# SheetV2.net
KiCad netlist of a schematic drawn in Altium Designer
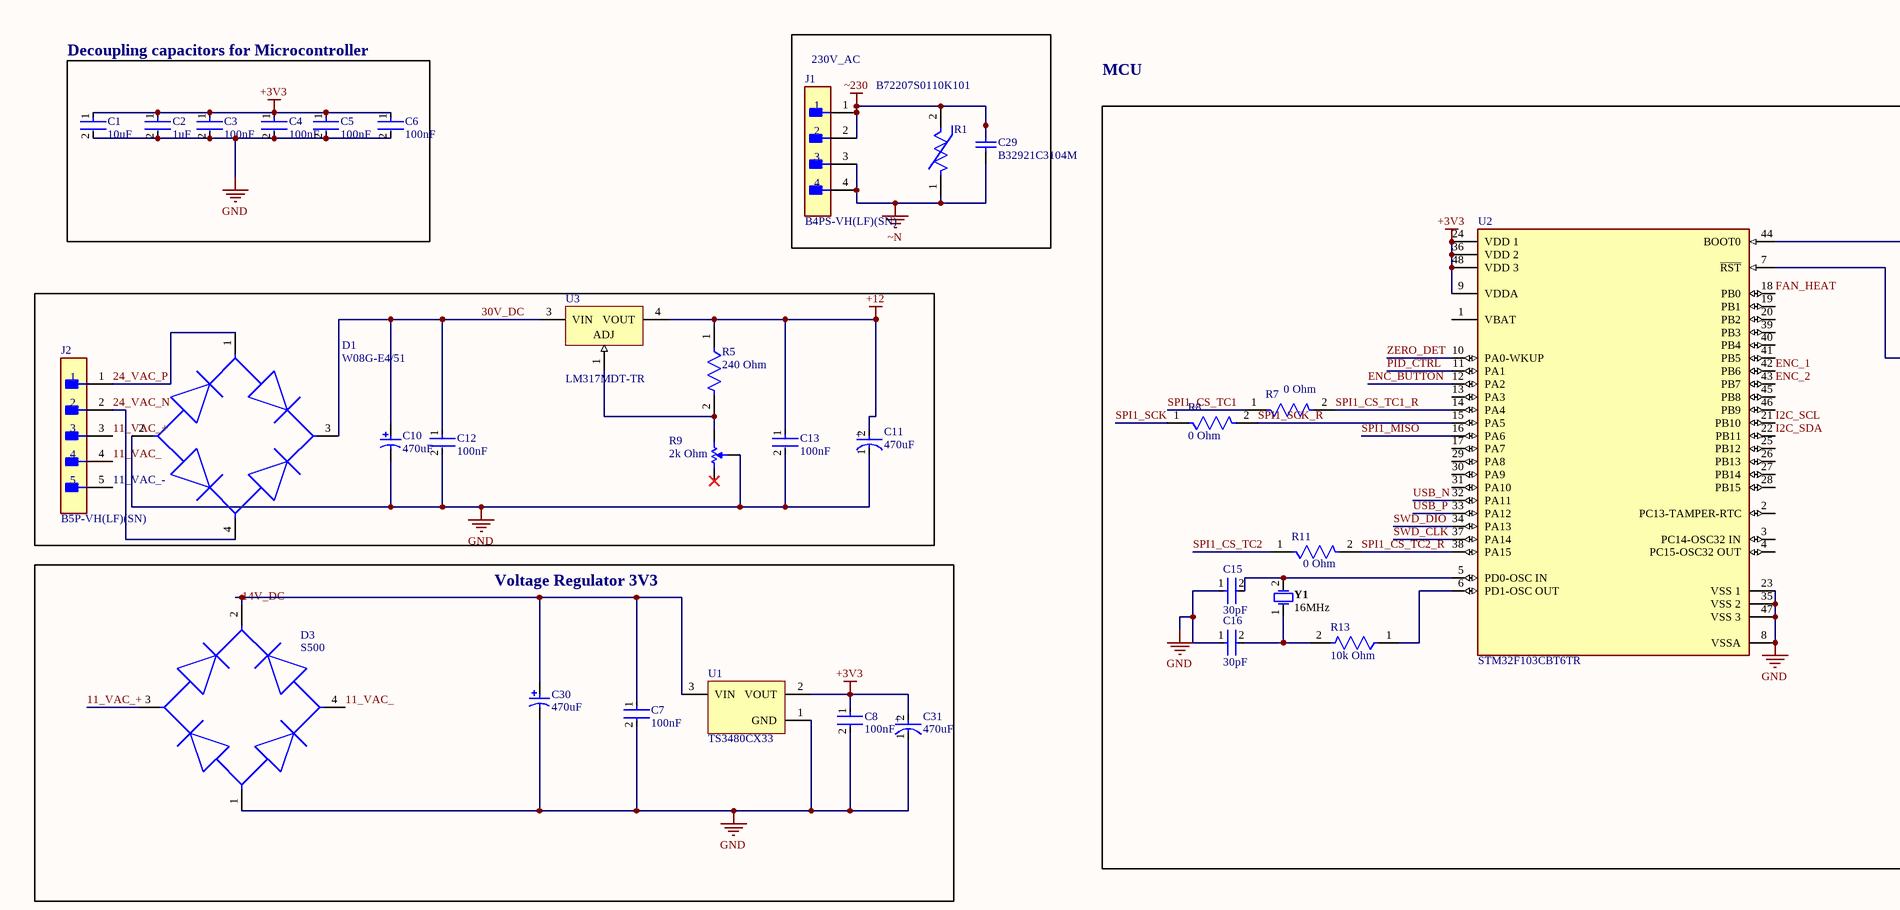
[diagram p0: SheetV2.SchDoc, top left]
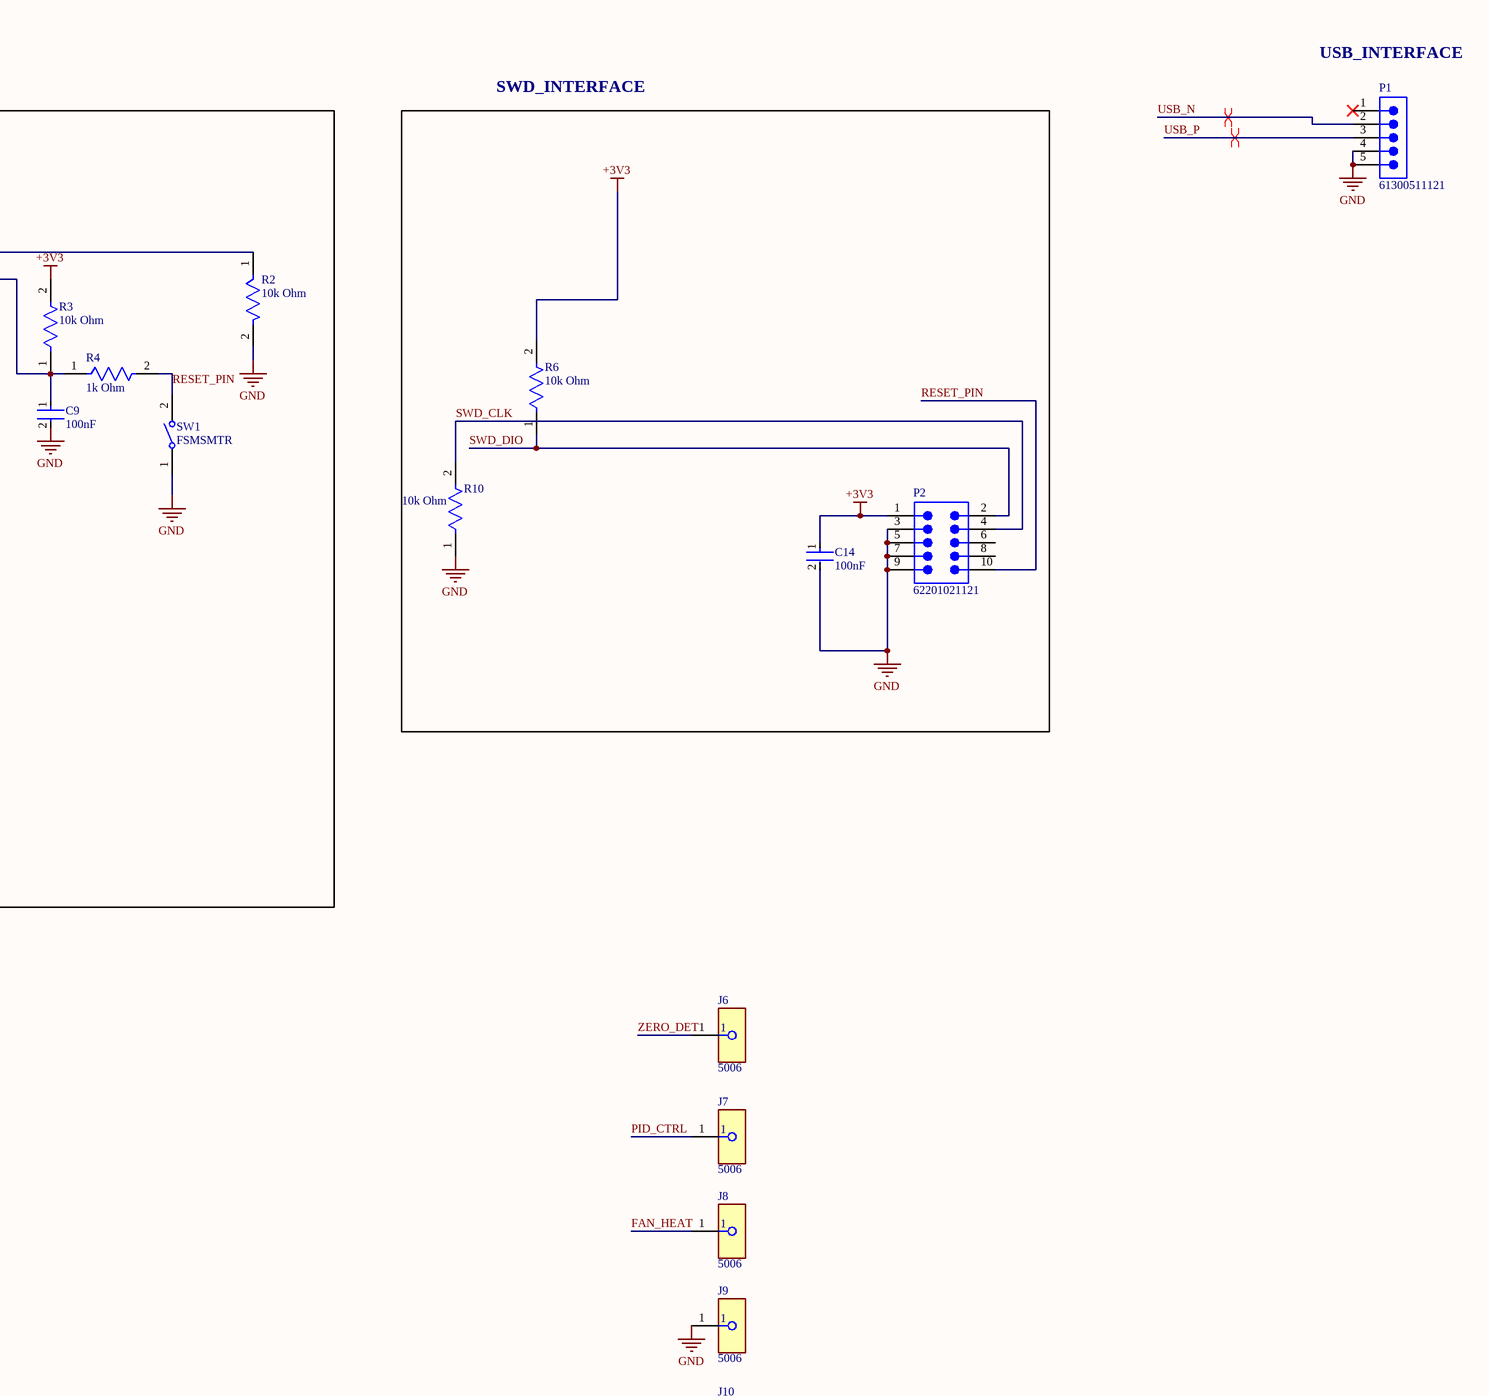
[diagram p1: SheetV2.SchDoc, top right]
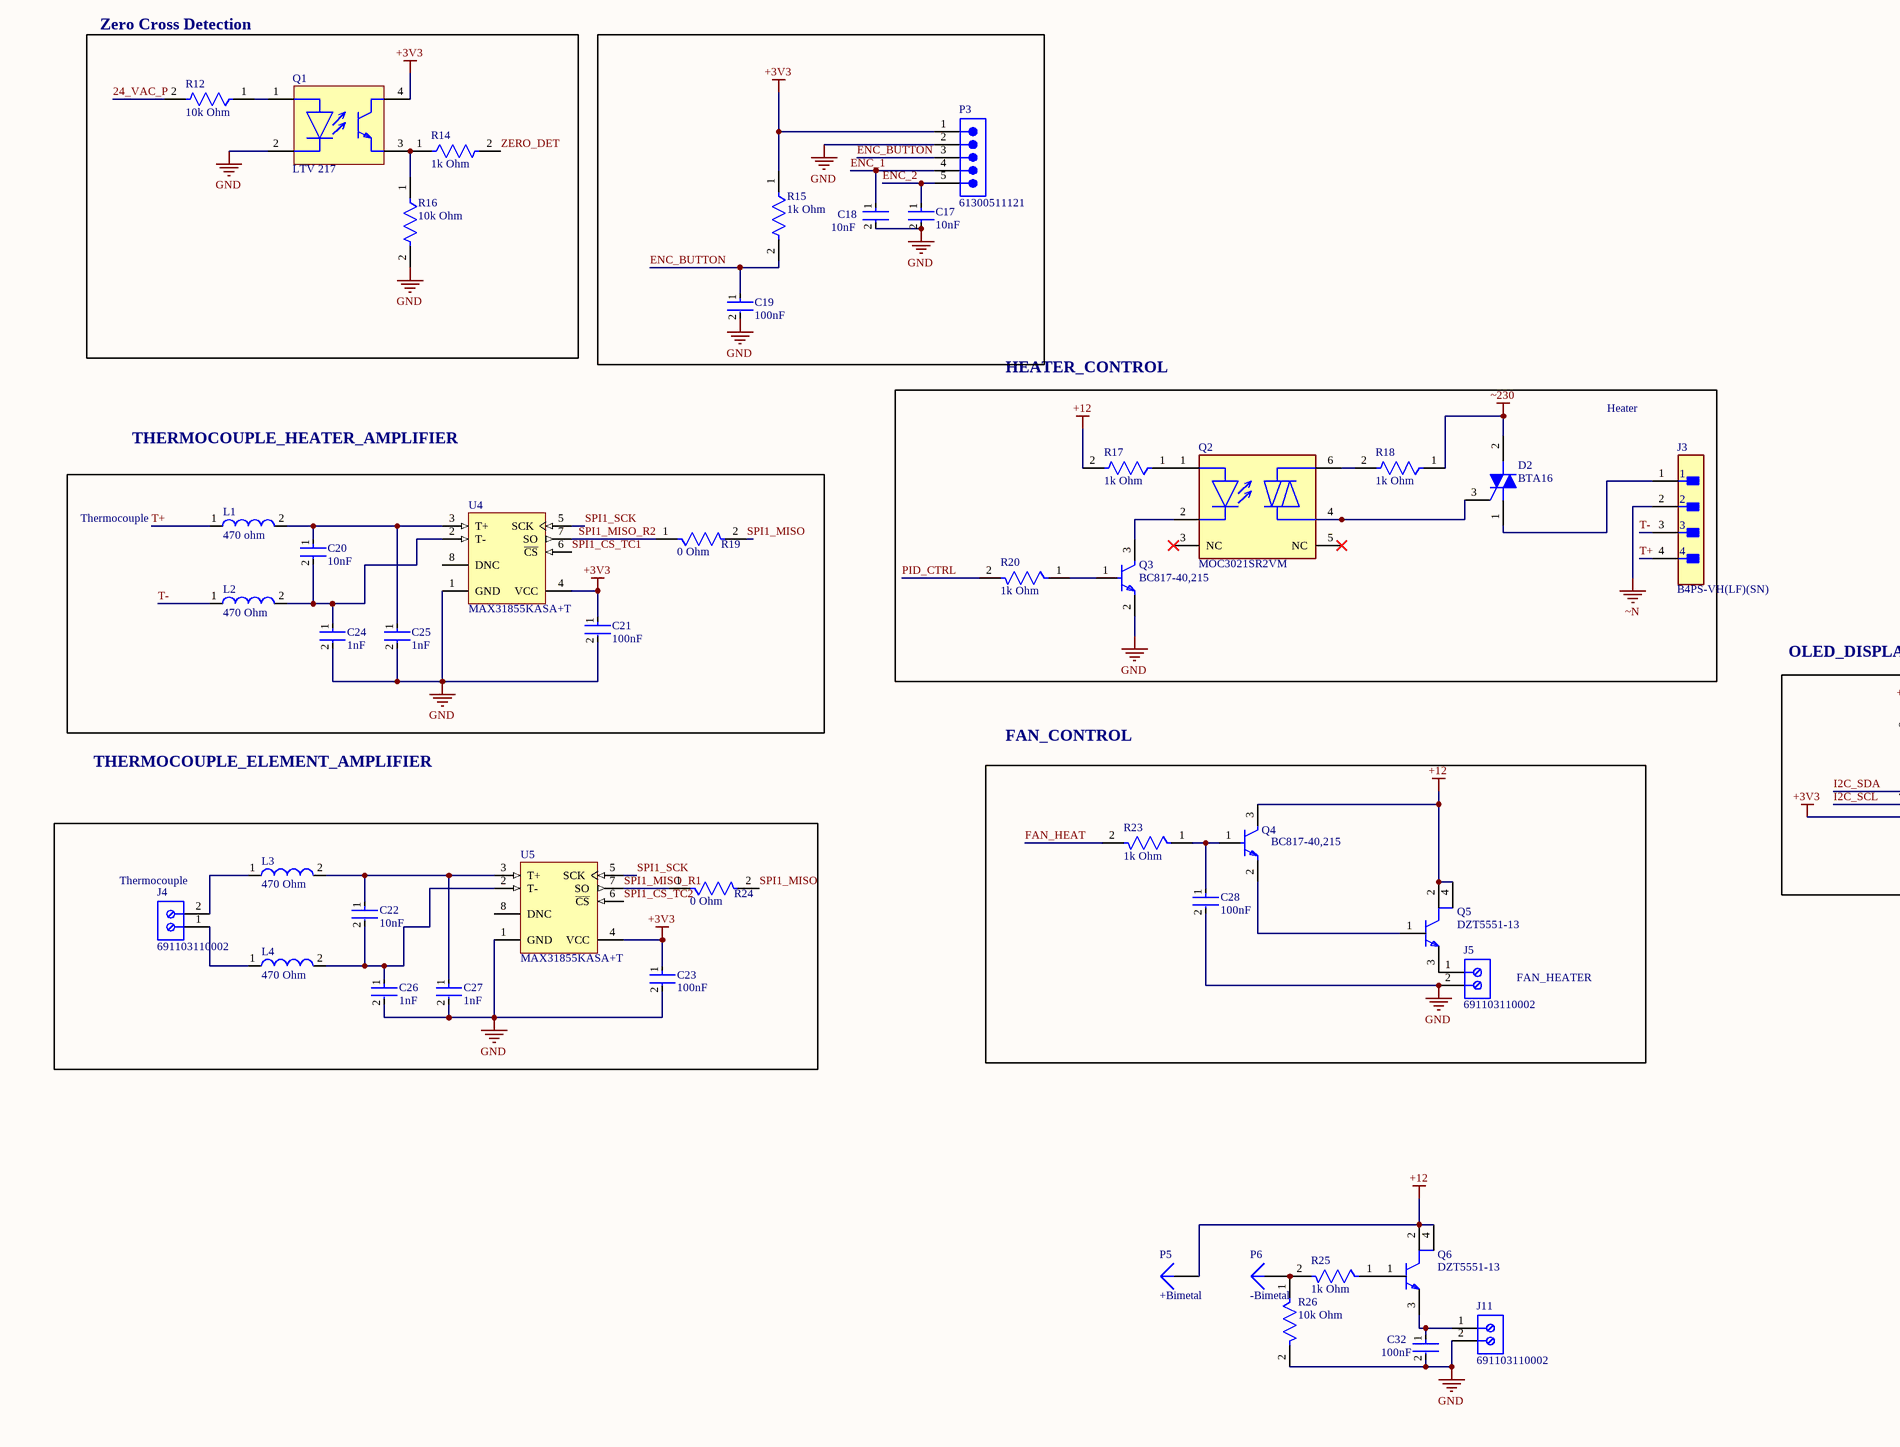
[diagram p2: SheetV2.SchDoc, bottom left]
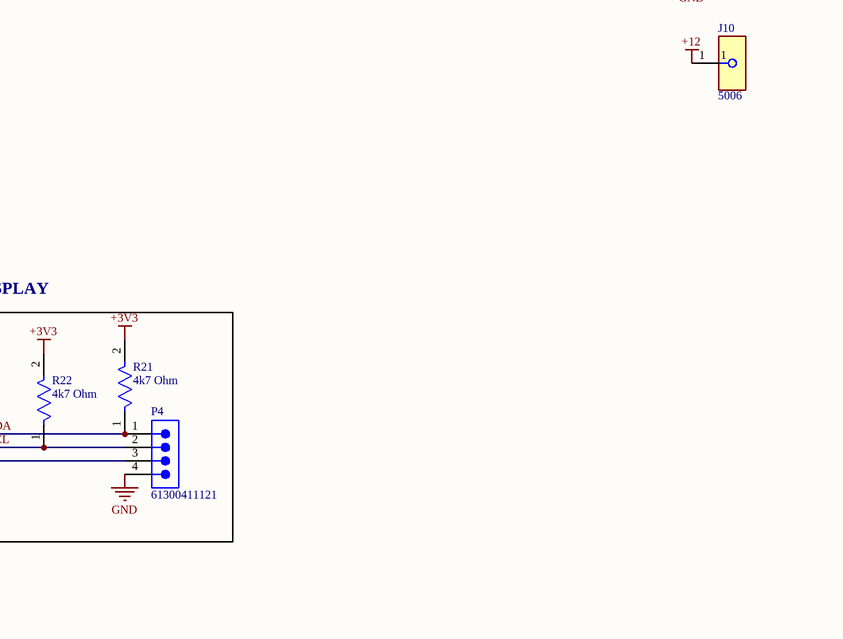
[diagram p3: SheetV2.SchDoc, bottom right]

(export (version "E")
  (design (tool "Eeschema 10.0.6"))
  (components
    (comp (ref "C1")
      (value "10uF")
      (footprint "FP-CC0805-0_85-MFG")
      (description "CAP CER 0.1UF 50V X7R 0805")
      (fields (field (name "TOLERANCE") "0.1") (field (name "MANUFACTURER PART NUMBER") "CC0805KRX7R9BB104"))
      (libsource (lib "Altium Content Vault") (part "11868f565c42a9108669ba33697ecf6"))
    )
    (comp (ref "C2")
      (value "1uF")
      (footprint "FP-CC0805-0_85-MFG")
      (description "CAP CER 0.1UF 50V X7R 0805")
      (fields (field (name "TOLERANCE") "0.1") (field (name "MANUFACTURER PART NUMBER") "CC0805KRX7R9BB104"))
      (libsource (lib "Altium Content Vault") (part "11868f565c42a9108669ba33697ecf6"))
    )
    (comp (ref "C3")
      (value "100nF")
      (footprint "FP-CC0805-0_85-MFG")
      (description "CAP CER 0.1UF 50V X7R 0805")
      (fields (field (name "TOLERANCE") "0.1") (field (name "MANUFACTURER PART NUMBER") "CC0805KRX7R9BB104"))
      (libsource (lib "Altium Content Vault") (part "11868f565c42a9108669ba33697ecf6"))
    )
    (comp (ref "C4")
      (value "100nF")
      (footprint "FP-CC0805-0_85-MFG")
      (description "CAP CER 0.1UF 50V X7R 0805")
      (fields (field (name "TOLERANCE") "0.1") (field (name "MANUFACTURER PART NUMBER") "CC0805KRX7R9BB104"))
      (libsource (lib "Altium Content Vault") (part "11868f565c42a9108669ba33697ecf6"))
    )
    (comp (ref "C5")
      (value "100nF")
      (footprint "FP-CC0805-0_85-MFG")
      (description "CAP CER 0.1UF 50V X7R 0805")
      (fields (field (name "TOLERANCE") "0.1") (field (name "MANUFACTURER PART NUMBER") "CC0805KRX7R9BB104"))
      (libsource (lib "Altium Content Vault") (part "11868f565c42a9108669ba33697ecf6"))
    )
    (comp (ref "C6")
      (value "100nF")
      (footprint "FP-CC0805-0_85-MFG")
      (description "CAP CER 0.1UF 50V X7R 0805")
      (fields (field (name "TOLERANCE") "0.1") (field (name "MANUFACTURER PART NUMBER") "CC0805KRX7R9BB104"))
      (libsource (lib "Altium Content Vault") (part "11868f565c42a9108669ba33697ecf6"))
    )
    (comp (ref "C7")
      (value "100nF")
      (footprint "FP-CC0805-0_85-MFG")
      (description "CAP CER 0.1UF 50V X7R 0805")
      (fields (field (name "TOLERANCE") "0.1") (field (name "MANUFACTURER PART NUMBER") "CC0805KRX7R9BB104"))
      (libsource (lib "Altium Content Vault") (part "11868f565c42a9108669ba33697ecf6"))
    )
    (comp (ref "C8")
      (value "100nF")
      (footprint "FP-CC0805-0_85-MFG")
      (description "CAP CER 0.1UF 50V X7R 0805")
      (fields (field (name "TOLERANCE") "0.1") (field (name "MANUFACTURER PART NUMBER") "CC0805KRX7R9BB104"))
      (libsource (lib "Altium Content Vault") (part "11868f565c42a9108669ba33697ecf6"))
    )
    (comp (ref "C9")
      (value "100nF")
      (footprint "FP-CC0805-0_85-MFG")
      (description "CAP CER 0.1UF 50V X7R 0805")
      (fields (field (name "TOLERANCE") "0.1") (field (name "MANUFACTURER PART NUMBER") "CC0805KRX7R9BB104"))
      (libsource (lib "Altium Content Vault") (part "11868f565c42a9108669ba33697ecf6"))
    )
    (comp (ref "C10")
      (value "470uF")
      (footprint "CAPPR65-500-2000X1000X2200")
      (description "Aluminum Electrolytic Capacitor, 470 uF, +/- 20%, 50 V, -40 to 85 degC, 2-Pin THD, RoHS, Bulk")
      (fields (field (name "TOLERANCE") "10%"))
      (libsource (lib "Altium Content Vault") (part "CAP-P-2"))
    )
    (comp (ref "C11")
      (value "470uF")
      (footprint "FP-RAD-TH-D_8_0_5-L_11_5-MFG")
      (description "Aluminum Electrolytic Capacitors (Radial Lead Type) 470uF ±20% 16V")
      (fields (field (name "TOLERANCE") "20%"))
      (libsource (lib "Altium Content Vault") (part "a00bbbee19879c290e62620ae7e47b1"))
    )
    (comp (ref "C12")
      (value "100nF")
      (footprint "FP-CC0805-0_85-MFG")
      (description "CAP CER 0.1UF 50V X7R 0805")
      (fields (field (name "TOLERANCE") "0.1") (field (name "MANUFACTURER PART NUMBER") "CC0805KRX7R9BB104"))
      (libsource (lib "Altium Content Vault") (part "11868f565c42a9108669ba33697ecf6"))
    )
    (comp (ref "C13")
      (value "100nF")
      (footprint "FP-CC0805-0_85-MFG")
      (description "CAP CER 0.1UF 50V X7R 0805")
      (fields (field (name "TOLERANCE") "0.1") (field (name "MANUFACTURER PART NUMBER") "CC0805KRX7R9BB104"))
      (libsource (lib "Altium Content Vault") (part "11868f565c42a9108669ba33697ecf6"))
    )
    (comp (ref "C14")
      (value "100nF")
      (footprint "FP-CC0805-0_85-MFG")
      (description "CAP CER 0.1UF 50V X7R 0805")
      (fields (field (name "TOLERANCE") "0.1") (field (name "MANUFACTURER PART NUMBER") "CC0805KRX7R9BB104"))
      (libsource (lib "Altium Content Vault") (part "11868f565c42a9108669ba33697ecf6"))
    )
    (comp (ref "C15")
      (value "30pF")
      (footprint "FP-CC0805-0_85-MFG")
      (description "CAP CER 0.1UF 50V X7R 0805")
      (fields (field (name "TOLERANCE") "0.1") (field (name "MANUFACTURER PART NUMBER") "CC0805KRX7R9BB104"))
      (libsource (lib "Altium Content Vault") (part "11868f565c42a9108669ba33697ecf6"))
    )
    (comp (ref "C16")
      (value "30pF")
      (footprint "FP-CC0805-0_85-MFG")
      (description "CAP CER 0.1UF 50V X7R 0805")
      (fields (field (name "TOLERANCE") "0.1") (field (name "MANUFACTURER PART NUMBER") "CC0805KRX7R9BB104"))
      (libsource (lib "Altium Content Vault") (part "11868f565c42a9108669ba33697ecf6"))
    )
    (comp (ref "C17")
      (value "10nF")
      (footprint "FP-CC0805-0_85-MFG")
      (description "CAP CER 0.1UF 50V X7R 0805")
      (fields (field (name "TOLERANCE") "0.1") (field (name "MANUFACTURER PART NUMBER") "CC0805KRX7R9BB104"))
      (libsource (lib "Altium Content Vault") (part "11868f565c42a9108669ba33697ecf6"))
    )
    (comp (ref "C18")
      (value "10nF")
      (footprint "FP-CC0805-0_85-MFG")
      (description "CAP CER 0.1UF 50V X7R 0805")
      (fields (field (name "TOLERANCE") "0.1") (field (name "MANUFACTURER PART NUMBER") "CC0805KRX7R9BB104"))
      (libsource (lib "Altium Content Vault") (part "11868f565c42a9108669ba33697ecf6"))
    )
    (comp (ref "C19")
      (value "100nF")
      (footprint "FP-CC0805-0_85-MFG")
      (description "CAP CER 0.1UF 50V X7R 0805")
      (fields (field (name "TOLERANCE") "0.1") (field (name "MANUFACTURER PART NUMBER") "CC0805KRX7R9BB104"))
      (libsource (lib "Altium Content Vault") (part "11868f565c42a9108669ba33697ecf6"))
    )
    (comp (ref "C20")
      (value "10nF")
      (footprint "FP-CC0805-0_85-MFG")
      (description "CAP CER 0.1UF 50V X7R 0805")
      (fields (field (name "TOLERANCE") "0.1") (field (name "MANUFACTURER PART NUMBER") "CC0805KRX7R9BB104"))
      (libsource (lib "Altium Content Vault") (part "11868f565c42a9108669ba33697ecf6"))
    )
    (comp (ref "C21")
      (value "100nF")
      (footprint "FP-CC0805-0_85-MFG")
      (description "CAP CER 0.1UF 50V X7R 0805")
      (fields (field (name "TOLERANCE") "0.1") (field (name "MANUFACTURER PART NUMBER") "CC0805KRX7R9BB104"))
      (libsource (lib "Altium Content Vault") (part "11868f565c42a9108669ba33697ecf6"))
    )
    (comp (ref "C22")
      (value "10nF")
      (footprint "FP-CC0805-0_85-MFG")
      (description "CAP CER 0.1UF 50V X7R 0805")
      (fields (field (name "TOLERANCE") "0.1") (field (name "MANUFACTURER PART NUMBER") "CC0805KRX7R9BB104"))
      (libsource (lib "Altium Content Vault") (part "11868f565c42a9108669ba33697ecf6"))
    )
    (comp (ref "C23")
      (value "100nF")
      (footprint "FP-CC0805-0_85-MFG")
      (description "CAP CER 0.1UF 50V X7R 0805")
      (fields (field (name "TOLERANCE") "0.1") (field (name "MANUFACTURER PART NUMBER") "CC0805KRX7R9BB104"))
      (libsource (lib "Altium Content Vault") (part "11868f565c42a9108669ba33697ecf6"))
    )
    (comp (ref "C24")
      (value "1nF")
      (footprint "FP-CC0805-0_85-MFG")
      (description "CAP CER 0.1UF 50V X7R 0805")
      (fields (field (name "TOLERANCE") "0.1") (field (name "MANUFACTURER PART NUMBER") "CC0805KRX7R9BB104"))
      (libsource (lib "Altium Content Vault") (part "11868f565c42a9108669ba33697ecf6"))
    )
    (comp (ref "C25")
      (value "1nF")
      (footprint "FP-CC0805-0_85-MFG")
      (description "CAP CER 0.1UF 50V X7R 0805")
      (fields (field (name "TOLERANCE") "0.1") (field (name "MANUFACTURER PART NUMBER") "CC0805KRX7R9BB104"))
      (libsource (lib "Altium Content Vault") (part "11868f565c42a9108669ba33697ecf6"))
    )
    (comp (ref "C26")
      (value "1nF")
      (footprint "FP-CC0805-0_85-MFG")
      (description "CAP CER 0.1UF 50V X7R 0805")
      (fields (field (name "TOLERANCE") "0.1") (field (name "MANUFACTURER PART NUMBER") "CC0805KRX7R9BB104"))
      (libsource (lib "Altium Content Vault") (part "11868f565c42a9108669ba33697ecf6"))
    )
    (comp (ref "C27")
      (value "1nF")
      (footprint "FP-CC0805-0_85-MFG")
      (description "CAP CER 0.1UF 50V X7R 0805")
      (fields (field (name "TOLERANCE") "0.1") (field (name "MANUFACTURER PART NUMBER") "CC0805KRX7R9BB104"))
      (libsource (lib "Altium Content Vault") (part "11868f565c42a9108669ba33697ecf6"))
    )
    (comp (ref "C28")
      (value "100nF")
      (footprint "FP-CC0805-0_85-MFG")
      (description "CAP CER 0.1UF 50V X7R 0805")
      (fields (field (name "TOLERANCE") "0.1") (field (name "MANUFACTURER PART NUMBER") "CC0805KRX7R9BB104"))
      (libsource (lib "Altium Content Vault") (part "11868f565c42a9108669ba33697ecf6"))
    )
    (comp (ref "C29")
      (value "B32921C3104M")
      (footprint "TDK-B32921C3104M")
      (description "EMI Suppression Capacitor (MKP), 0.1 uF, +/- 20%, 305 V, 2-Pin THD, RoHS, Bulk")
      (fields (field (name "MANUFACTURER") "TDK") (field (name "TOLERANCE") "±20%"))
      (libsource (lib "Altium Content Vault") (part "CAP-NP-2"))
    )
    (comp (ref "C30")
      (value "470uF")
      (footprint "CAPPR65-500-2000X1000X2200")
      (description "Aluminum Electrolytic Capacitor, 470 uF, +/- 20%, 50 V, -40 to 85 degC, 2-Pin THD, RoHS, Bulk")
      (fields (field (name "TOLERANCE") "10%"))
      (libsource (lib "Altium Content Vault") (part "CAP-P-2"))
    )
    (comp (ref "C31")
      (value "470uF")
      (footprint "FP-RAD-TH-D_8_0_5-L_11_5-MFG")
      (description "Aluminum Electrolytic Capacitors (Radial Lead Type) 470uF ±20% 16V")
      (fields (field (name "TOLERANCE") "20%"))
      (libsource (lib "Altium Content Vault") (part "a00bbbee19879c290e62620ae7e47b1"))
    )
    (comp (ref "C32")
      (value "100nF")
      (footprint "FP-CC0805-0_85-MFG")
      (description "CAP CER 0.1UF 50V X7R 0805")
      (fields (field (name "TOLERANCE") "0.1") (field (name "MANUFACTURER PART NUMBER") "CC0805KRX7R9BB104"))
      (libsource (lib "Altium Content Vault") (part "11868f565c42a9108669ba33697ecf6"))
    )
    (comp (ref "D1")
      (value "W08G-E4/51")
      (footprint "FP-WOG-MFG")
      (description "W08G-E4/51 Diode Rectifier Bridge Single 800V 1.5A 4-Pin Case WOG Bulk")
      (libsource (lib "Altium Content Vault") (part "7f679ecdc54638986ed3433d0c5b104"))
    )
    (comp (ref "D2")
      (value "BTA16")
      (footprint "ONSC-TO-220-3-221A-09")
      (description "Sensitive Gate Triacs, Silicon Bidirectional Thyristor, 3-Pin TO-220, Pb-Free, Bulk Box")
      (fields (field (name "PARTNUMBER") "MAC228A6G") (field (name "MANUFACTURER") "On Semiconductor"))
      (libsource (lib "Altium Content Vault") (part "ONSC-TRIAC-MT1MT2G-3"))
    )
    (comp (ref "D3")
      (value "S500")
      (footprint "FP-MB2S-E3-80-MFG")
      (description "BRIDGE RECT 1P 200V TO269AA")
      (libsource (lib "Altium Content Vault") (part "c9830caf88b611fe4a3296c074f7a67"))
    )
    (comp (ref "J1")
      (value "B4PS-VH(LF)(SN)")
      (footprint "FP-B4PS-VH_LF_SN-MFG")
      (description "CONN HEADER R/A 4POS 3.96MM")
      (libsource (lib "") (part "299a8cea1bdcbc3624fe62c390fa72c_1"))
    )
    (comp (ref "J2")
      (value "B5P-VH(LF)(SN)")
      (footprint "FP-B5P-VH_LF_SN-MFG")
      (description "CONN HEADER VERT 5POS 3.96MM")
      (libsource (lib "Altium Content Vault") (part "051ac7c1f60a91215dd69c4e70fad1a"))
    )
    (comp (ref "J3")
      (value "B4PS-VH(LF)(SN)")
      (footprint "FP-B4PS-VH_LF_SN-MFG")
      (description "CONN HEADER R/A 4POS 3.96MM")
      (libsource (lib "Altium Content Vault") (part "299a8cea1bdcbc3624fe62c390fa72c"))
    )
    (comp (ref "J4")
      (value "691103110002")
      (footprint "691103110002")
      (fields (field (name "VOLTAGE") "125V"))
      (libsource (lib "Altium Content Vault") (part "TBL - 1R - 02P - Screw"))
    )
    (comp (ref "J5")
      (value "691103110002")
      (footprint "691103110002")
      (fields (field (name "VOLTAGE") "125V"))
      (libsource (lib "Altium Content Vault") (part "TBL - 1R - 02P - Screw"))
    )
    (comp (ref "J6")
      (value "5006")
      (footprint "FP-5006-MFG")
      (description "PC TEST POINT COMPACT BLACK")
      (libsource (lib "Altium Content Vault") (part "98815daf2f2c152b0c43f5ab9800df6"))
    )
    (comp (ref "J7")
      (value "5006")
      (footprint "FP-5006-MFG")
      (description "PC TEST POINT COMPACT BLACK")
      (libsource (lib "Altium Content Vault") (part "98815daf2f2c152b0c43f5ab9800df6"))
    )
    (comp (ref "J8")
      (value "5006")
      (footprint "FP-5006-MFG")
      (description "PC TEST POINT COMPACT BLACK")
      (libsource (lib "Altium Content Vault") (part "98815daf2f2c152b0c43f5ab9800df6"))
    )
    (comp (ref "J9")
      (value "5006")
      (footprint "FP-5006-MFG")
      (description "PC TEST POINT COMPACT BLACK")
      (libsource (lib "Altium Content Vault") (part "98815daf2f2c152b0c43f5ab9800df6"))
    )
    (comp (ref "J10")
      (value "5006")
      (footprint "FP-5006-MFG")
      (description "PC TEST POINT COMPACT BLACK")
      (libsource (lib "Altium Content Vault") (part "98815daf2f2c152b0c43f5ab9800df6"))
    )
    (comp (ref "J11")
      (value "691103110002")
      (footprint "691103110002")
      (fields (field (name "VOLTAGE") "125V"))
      (libsource (lib "Altium Content Vault") (part "TBL - 1R - 02P - Screw"))
    )
    (comp (ref "L1")
      (value "470 ohm")
      (footprint "SMD-0805")
      (description "SMD EMI Suppression Ferrite Bead WE-CBF, Z = 470 Ohm")
      (libsource (lib "Altium Content Vault") (part "PAS-IND-INDUCTOR-2"))
    )
    (comp (ref "L2")
      (value "470 Ohm")
      (footprint "SMD-0805")
      (description "SMD EMI Suppression Ferrite Bead WE-CBF, Z = 470 Ohm")
      (libsource (lib "Altium Content Vault") (part "PAS-IND-INDUCTOR-2"))
    )
    (comp (ref "L3")
      (value "470 Ohm")
      (footprint "SMD-0805")
      (description "SMD EMI Suppression Ferrite Bead WE-CBF, Z = 470 Ohm")
      (libsource (lib "Altium Content Vault") (part "PAS-IND-INDUCTOR-2"))
    )
    (comp (ref "L4")
      (value "470 Ohm")
      (footprint "SMD-0805")
      (description "SMD EMI Suppression Ferrite Bead WE-CBF, Z = 470 Ohm")
      (libsource (lib "Altium Content Vault") (part "PAS-IND-INDUCTOR-2"))
    )
    (comp (ref "P1")
      (value "61300511121")
      (footprint "61300511121")
      (libsource (lib "Altium Content Vault") (part "Header_Male_1R_05P"))
    )
    (comp (ref "P2")
      (value "62201021121")
      (footprint "62201021121")
      (libsource (lib "Altium Content Vault") (part "Header_Male_2R_10P"))
    )
    (comp (ref "P3")
      (value "61300511121")
      (footprint "61300511121")
      (libsource (lib "Altium Content Vault") (part "Header_Male_1R_05P"))
    )
    (comp (ref "P4")
      (value "61300411121")
      (footprint "61300411121")
      (libsource (lib "Altium Content Vault") (part "Header_Male_1R_04P"))
    )
    (comp (ref "P5")
      (value "+Bimetal")
      (footprint "PIN1")
      (description "Plug")
      (fields (field (name "PUBLISHER") "Altium Limited"))
      (libsource (lib "Miscellaneous Connectors") (part "Plug"))
    )
    (comp (ref "P6")
      (value "-Bimetal")
      (footprint "PIN1")
      (description "Plug")
      (fields (field (name "PUBLISHER") "Altium Limited"))
      (libsource (lib "Miscellaneous Connectors") (part "Plug"))
    )
    (comp (ref "Q1")
      (value "LTV 217")
      (footprint "SOP127P700X210_HS-5_SO4-Opto2_N")
      (description "Optocoupler DC-IN 1-CH Transistor DC-OUT 4-Pin SSOP Embossed T/R")
      (libsource (lib "Altium Content Vault") (part "f4732c5a005c16655bf03302f8bd1cc"))
    )
    (comp (ref "Q2")
      (value "MOC3021SR2VM")
      (footprint "FP-646BY-MFG")
      (description "MOC3021SR2VM Triac Driver Output Optocoupler, 6-Pin DIP 400V Random Phase")
      (libsource (lib "Altium Content Vault") (part "315d33d7a3de83856d3bd334bf87c2f"))
    )
    (comp (ref "Q3")
      (value "BC817-40,215")
      (footprint "FP-SOT23-MFG")
      (description "TRANS NPN 45V 0.5A SOT23")
      (fields
        (field (name "OCTOPART") "https://octopart.com/bc817-40%2C215-nexperia-78739081")
        (field (name "MANUFACTURER") "Nexperia")
      )
      (libsource (lib "Altium Content Vault") (part "b44e953556f554d0102664c7d152cb4"))
    )
    (comp (ref "Q4")
      (value "BC817-40,215")
      (footprint "FP-SOT23-MFG")
      (description "TRANS NPN 45V 0.5A SOT23")
      (fields
        (field (name "OCTOPART") "https://octopart.com/bc817-40%2C215-nexperia-78739081")
        (field (name "MANUFACTURER") "Nexperia")
      )
      (libsource (lib "Altium Content Vault") (part "b44e953556f554d0102664c7d152cb4"))
    )
    (comp (ref "Q5")
      (value "DZT5551-13")
      (footprint "FP-SOT223-MFG")
      (description "TRANS NPN 160V 0.6A SOT-223")
      (fields
        (field (name "MANUFACTURER") "Diodes")
        (field (name "OCTOPART") "https://octopart.com/dzt5551-13-diodes+inc.-12426785")
      )
      (libsource (lib "Altium Content Vault") (part "ef0222921274e2dfe3c88fb5f98777d"))
    )
    (comp (ref "Q6")
      (value "DZT5551-13")
      (footprint "FP-SOT223-MFG")
      (description "TRANS NPN 160V 0.6A SOT-223")
      (fields
        (field (name "MANUFACTURER") "Diodes")
        (field (name "OCTOPART") "https://octopart.com/dzt5551-13-diodes+inc.-12426785")
      )
      (libsource (lib "Altium Content Vault") (part "ef0222921274e2dfe3c88fb5f98777d"))
    )
    (comp (ref "R1")
      (value "B72207S0110K101")
      (footprint "FP-B72207S0110K101-MFG")
      (description "VARISTOR 18V 250A DISC 7MM")
      (fields
        (field (name "MANUFACTURER") "EPCOS")
        (field (name "OCTOPART") "https://octopart.com/b72207s0110k101-epcos-11931358")
      )
      (libsource (lib "Altium Content Vault") (part "78a88060d5b7b043d6e48adc4284376"))
    )
    (comp (ref "R2")
      (value "10k Ohm")
      (footprint "FP-RMCF0805-MFG")
      (description "RES 0 OHM JUMPER 1/8W 0805")
      (libsource (lib "Altium Content Vault") (part "1029c3af85768c4190bb7ad29bc67b5"))
    )
    (comp (ref "R3")
      (value "10k Ohm")
      (footprint "FP-RMCF0805-MFG")
      (description "RES 0 OHM JUMPER 1/8W 0805")
      (libsource (lib "Altium Content Vault") (part "1029c3af85768c4190bb7ad29bc67b5"))
    )
    (comp (ref "R4")
      (value "1k Ohm")
      (footprint "FP-RMCF0805-MFG")
      (description "RES 0 OHM JUMPER 1/8W 0805")
      (libsource (lib "Altium Content Vault") (part "1029c3af85768c4190bb7ad29bc67b5"))
    )
    (comp (ref "R5")
      (value "240 Ohm")
      (footprint "FP-RMCF0805-MFG")
      (description "RES 0 OHM JUMPER 1/8W 0805")
      (libsource (lib "Altium Content Vault") (part "1029c3af85768c4190bb7ad29bc67b5"))
    )
    (comp (ref "R6")
      (value "10k Ohm")
      (footprint "FP-RMCF0805-MFG")
      (description "RES 0 OHM JUMPER 1/8W 0805")
      (libsource (lib "Altium Content Vault") (part "1029c3af85768c4190bb7ad29bc67b5"))
    )
    (comp (ref "R7")
      (value "0 Ohm")
      (footprint "FP-RMCF0805-MFG")
      (description "RES 0 OHM JUMPER 1/8W 0805")
      (libsource (lib "Altium Content Vault") (part "1029c3af85768c4190bb7ad29bc67b5"))
    )
    (comp (ref "R8")
      (value "0 Ohm")
      (footprint "FP-RMCF0805-MFG")
      (description "RES 0 OHM JUMPER 1/8W 0805")
      (libsource (lib "Altium Content Vault") (part "1029c3af85768c4190bb7ad29bc67b5"))
    )
    (comp (ref "R9")
      (value "2k Ohm")
      (footprint "BOUR-3296W-1-3")
      (description "Square Trimpot(R) Trimming Potentiometer, 1000 Ohm, -55 to 125 degC, 3-Pin THD, RoHS, Tube")
      (fields (field (name "TOLERANCE") "1%"))
      (libsource (lib "Altium Content Vault") (part "RES-ADJ-3"))
    )
    (comp (ref "R10")
      (value "10k Ohm")
      (footprint "FP-RMCF0805-MFG")
      (description "RES 0 OHM JUMPER 1/8W 0805")
      (libsource (lib "Altium Content Vault") (part "1029c3af85768c4190bb7ad29bc67b5"))
    )
    (comp (ref "R11")
      (value "0 Ohm")
      (footprint "FP-RMCF0805-MFG")
      (description "RES 0 OHM JUMPER 1/8W 0805")
      (libsource (lib "Altium Content Vault") (part "1029c3af85768c4190bb7ad29bc67b5"))
    )
    (comp (ref "R12")
      (value "10k Ohm")
      (footprint "FP-RMCF0805-MFG")
      (description "RES 0 OHM JUMPER 1/8W 0805")
      (libsource (lib "Altium Content Vault") (part "1029c3af85768c4190bb7ad29bc67b5"))
    )
    (comp (ref "R13")
      (value "10k Ohm")
      (footprint "FP-RMCF0805-MFG")
      (description "RES 0 OHM JUMPER 1/8W 0805")
      (libsource (lib "Altium Content Vault") (part "1029c3af85768c4190bb7ad29bc67b5"))
    )
    (comp (ref "R14")
      (value "1k Ohm")
      (footprint "FP-RMCF0805-MFG")
      (description "RES 0 OHM JUMPER 1/8W 0805")
      (libsource (lib "Altium Content Vault") (part "1029c3af85768c4190bb7ad29bc67b5"))
    )
    (comp (ref "R15")
      (value "1k Ohm")
      (footprint "FP-RMCF0805-MFG")
      (description "RES 0 OHM JUMPER 1/8W 0805")
      (libsource (lib "Altium Content Vault") (part "1029c3af85768c4190bb7ad29bc67b5"))
    )
    (comp (ref "R16")
      (value "10k Ohm")
      (footprint "FP-RMCF0805-MFG")
      (description "RES 0 OHM JUMPER 1/8W 0805")
      (libsource (lib "Altium Content Vault") (part "1029c3af85768c4190bb7ad29bc67b5"))
    )
    (comp (ref "R17")
      (value "1k Ohm")
      (footprint "FP-RMCF0805-MFG")
      (description "RES 0 OHM JUMPER 1/8W 0805")
      (libsource (lib "Altium Content Vault") (part "1029c3af85768c4190bb7ad29bc67b5"))
    )
    (comp (ref "R18")
      (value "1k Ohm")
      (footprint "FP-RMCF0805-MFG")
      (description "RES 0 OHM JUMPER 1/8W 0805")
      (libsource (lib "Altium Content Vault") (part "1029c3af85768c4190bb7ad29bc67b5"))
    )
    (comp (ref "R19")
      (value "0 Ohm")
      (footprint "FP-RMCF0805-MFG")
      (description "RES 0 OHM JUMPER 1/8W 0805")
      (libsource (lib "Altium Content Vault") (part "1029c3af85768c4190bb7ad29bc67b5"))
    )
    (comp (ref "R20")
      (value "1k Ohm")
      (footprint "FP-RMCF0805-MFG")
      (description "RES 0 OHM JUMPER 1/8W 0805")
      (libsource (lib "Altium Content Vault") (part "1029c3af85768c4190bb7ad29bc67b5"))
    )
    (comp (ref "R21")
      (value "4k7 Ohm")
      (footprint "FP-RMCF0805-MFG")
      (description "RES 0 OHM JUMPER 1/8W 0805")
      (libsource (lib "Altium Content Vault") (part "1029c3af85768c4190bb7ad29bc67b5"))
    )
    (comp (ref "R22")
      (value "4k7 Ohm")
      (footprint "FP-RMCF0805-MFG")
      (description "RES 0 OHM JUMPER 1/8W 0805")
      (libsource (lib "Altium Content Vault") (part "1029c3af85768c4190bb7ad29bc67b5"))
    )
    (comp (ref "R23")
      (value "1k Ohm")
      (footprint "FP-RMCF0805-MFG")
      (description "RES 0 OHM JUMPER 1/8W 0805")
      (libsource (lib "Altium Content Vault") (part "1029c3af85768c4190bb7ad29bc67b5"))
    )
    (comp (ref "R24")
      (value "0 Ohm")
      (footprint "FP-RMCF0805-MFG")
      (description "RES 0 OHM JUMPER 1/8W 0805")
      (libsource (lib "Altium Content Vault") (part "1029c3af85768c4190bb7ad29bc67b5"))
    )
    (comp (ref "R25")
      (value "1k Ohm")
      (footprint "FP-RMCF0805-MFG")
      (description "RES 0 OHM JUMPER 1/8W 0805")
      (libsource (lib "Altium Content Vault") (part "1029c3af85768c4190bb7ad29bc67b5"))
    )
    (comp (ref "R26")
      (value "10k Ohm")
      (footprint "FP-RMCF0805-MFG")
      (description "RES 0 OHM JUMPER 1/8W 0805")
      (libsource (lib "Altium Content Vault") (part "1029c3af85768c4190bb7ad29bc67b5"))
    )
    (comp (ref "SW1")
      (value "FSMSMTR")
      (footprint "TECO-FSMSMTR_V")
      (description "FSMSM Push Button Switch, 50 mA, -35 to 85 degC, 2-Pin SMD, RoHS, Tape and Reel")
      (fields (field (name "MANUFACTURER") "TE Connectivity"))
      (libsource (lib "Altium Content Vault") (part "SW-SPST-2_C"))
    )
    (comp (ref "U1")
      (value "TS3480CX33")
      (footprint "SOT-23-TT3_L")
      (description "Low Quiescent Current LDO, 3-Pin SOT-23, Extended Temperature, Tape and Reel")
      (libsource (lib "Altium Content Vault") (part "PM-LINEREG-MCP1700-IL3"))
    )
    (comp (ref "U2")
      (value "STM32F103CBT6TR")
      (footprint "FP-LQFP48-5B-MFG")
      (libsource (lib "Altium Content Vault") (part "2bc3fe5586cf3d28b17275e4580a88a"))
    )
    (comp (ref "U3")
      (value "LM317MDT-TR")
      (footprint "TO-252_L")
      (description "500mA, Medium Current 1.2 to 37 V Adjustable Voltage Regulator, 3-Pin DPAK, Tape and Reel")
      (libsource (lib "Altium Content Vault") (part "PM-REG-LM217M-SOT3"))
    )
    (comp (ref "U4")
      (value "MAX31855KASA+T")
      (footprint "MAXM-S8+4_N")
      (fields (field (name "GENERIC PART NUMBER") "MAX31855"))
      (libsource (lib "Altium Content Vault") (part "MAX31855-S8+4"))
    )
    (comp (ref "U5")
      (value "MAX31855KASA+T")
      (footprint "MAXM-S8+4_N")
      (fields (field (name "GENERIC PART NUMBER") "MAX31855"))
      (libsource (lib "Altium Content Vault") (part "MAX31855-S8+4"))
    )
    (comp (ref "Y1")
      (value "16MHz")
      (footprint "FOX-FOXSLF160-20")
      (description "Resistance Weld Thru-Hole Crystal, 16 MHz, -20 to 70 degC, 2-Pin THD, RoHS, Bulk")
      (fields (field (name "TOLERANCE") "1%"))
      (libsource (lib "Altium Content Vault") (part "XTAL-1-2-2"))
    )
  )
  (nets
    (net (code "1") (name "+3V3") (class "Default")
      (node (ref "C1") (pin "1") (pinfunction "1_1") (pintype "passive"))
      (node (ref "C14") (pin "1") (pinfunction "1_1") (pintype "passive"))
      (node (ref "C2") (pin "1") (pinfunction "1_1") (pintype "passive"))
      (node (ref "C21") (pin "1") (pinfunction "1_1") (pintype "passive"))
      (node (ref "C23") (pin "1") (pinfunction "1_1") (pintype "passive"))
      (node (ref "C3") (pin "1") (pinfunction "1_1") (pintype "passive"))
      (node (ref "C31") (pin "2") (pinfunction "A_2") (pintype "passive"))
      (node (ref "C4") (pin "1") (pinfunction "1_1") (pintype "passive"))
      (node (ref "C5") (pin "1") (pinfunction "1_1") (pintype "passive"))
      (node (ref "C6") (pin "1") (pinfunction "1_1") (pintype "passive"))
      (node (ref "C8") (pin "1") (pinfunction "1_1") (pintype "passive"))
      (node (ref "P2") (pin "1") (pinfunction "1_1") (pintype "passive"))
      (node (ref "P3") (pin "1") (pinfunction "1_1") (pintype "passive"))
      (node (ref "P4") (pin "3") (pinfunction "3_3") (pintype "passive"))
      (node (ref "Q1") (pin "4") (pinfunction "C_4") (pintype "passive"))
      (node (ref "R15") (pin "1") (pinfunction "1_1") (pintype "passive"))
      (node (ref "R21") (pin "2") (pinfunction "2_2") (pintype "passive"))
      (node (ref "R22") (pin "2") (pinfunction "2_2") (pintype "passive"))
      (node (ref "R3") (pin "2") (pinfunction "2_2") (pintype "passive"))
      (node (ref "R6") (pin "2") (pinfunction "2_2") (pintype "passive"))
      (node (ref "U1") (pin "2") (pinfunction "VOUT_2") (pintype "power_in"))
      (node (ref "U2") (pin "24") (pinfunction "VDD_1_24") (pintype "power_in"))
      (node (ref "U2") (pin "36") (pinfunction "VDD_2_36") (pintype "power_in"))
      (node (ref "U2") (pin "48") (pinfunction "VDD_3_48") (pintype "power_in"))
      (node (ref "U2") (pin "9") (pinfunction "VDDA_9") (pintype "power_in"))
      (node (ref "U4") (pin "4") (pinfunction "VCC_4") (pintype "power_in"))
      (node (ref "U5") (pin "4") (pinfunction "VCC_4") (pintype "power_in"))
    )
    (net (code "2") (name "+12") (class "Default")
      (node (ref "C11") (pin "2") (pinfunction "A_2") (pintype "passive"))
      (node (ref "C13") (pin "1") (pinfunction "1_1") (pintype "passive"))
      (node (ref "J10") (pin "1") (pinfunction "1_1") (pintype "passive"))
      (node (ref "P5") (pin "1") (pinfunction "1_1") (pintype "passive"))
      (node (ref "Q4") (pin "3") (pinfunction "C_3") (pintype "passive"))
      (node (ref "Q5") (pin "2") (pinfunction "C_2") (pintype "passive"))
      (node (ref "Q5") (pin "4") (pinfunction "C_4") (pintype "passive"))
      (node (ref "Q6") (pin "2") (pinfunction "C_2") (pintype "passive"))
      (node (ref "Q6") (pin "4") (pinfunction "C_4") (pintype "passive"))
      (node (ref "R17") (pin "2") (pinfunction "2_2") (pintype "passive"))
      (node (ref "R5") (pin "1") (pinfunction "1_1") (pintype "passive"))
      (node (ref "U3") (pin "4") (pinfunction "VOUT_4") (pintype "power_in"))
    )
    (net (code "3") (name "/11_VAC_") (class "Default")
      (node (ref "D3") (pin "4") (pinfunction "2_~_4") (pintype "passive"))
      (node (ref "J2") (pin "4") (pinfunction "4_4") (pintype "passive"))
    )
    (net (code "4") (name "/11_VAC_+") (class "Default")
      (node (ref "D3") (pin "3") (pinfunction "1_~_3") (pintype "passive"))
      (node (ref "J2") (pin "3") (pinfunction "3_3") (pintype "passive"))
    )
    (net (code "5") (name "/14V_DC") (class "Default")
      (node (ref "C30") (pin "1") (pinfunction "1_1") (pintype "passive"))
      (node (ref "C7") (pin "1") (pinfunction "1_1") (pintype "passive"))
      (node (ref "D3") (pin "2") (pinfunction "A_2") (pintype "passive"))
      (node (ref "U1") (pin "3") (pinfunction "VIN_3") (pintype "power_in"))
    )
    (net (code "6") (name "/24_VAC_N") (class "Default")
      (node (ref "D1") (pin "4") (pinfunction "2_~_4") (pintype "passive"))
      (node (ref "J2") (pin "2") (pinfunction "2_2") (pintype "passive"))
    )
    (net (code "7") (name "/24_VAC_P") (class "Default")
      (node (ref "D1") (pin "1") (pinfunction "1_~_1") (pintype "passive"))
      (node (ref "J2") (pin "1") (pinfunction "1_1") (pintype "passive"))
      (node (ref "R12") (pin "2") (pinfunction "2_2") (pintype "passive"))
    )
    (net (code "8") (name "/30V_DC") (class "Default")
      (node (ref "C10") (pin "1") (pinfunction "1_1") (pintype "passive"))
      (node (ref "C12") (pin "1") (pinfunction "1_1") (pintype "passive"))
      (node (ref "D1") (pin "3") (pinfunction "-_3") (pintype "passive"))
      (node (ref "U3") (pin "3") (pinfunction "VIN_3") (pintype "power_in"))
    )
    (net (code "9") (name "/ENC_1") (class "Default")
      (node (ref "C18") (pin "1") (pinfunction "1_1") (pintype "passive"))
      (node (ref "P3") (pin "4") (pinfunction "4_4") (pintype "passive"))
      (node (ref "U2") (pin "42") (pinfunction "PB6_42") (pintype "bidirectional"))
    )
    (net (code "10") (name "/ENC_2") (class "Default")
      (node (ref "C17") (pin "1") (pinfunction "1_1") (pintype "passive"))
      (node (ref "P3") (pin "5") (pinfunction "5_5") (pintype "passive"))
      (node (ref "U2") (pin "43") (pinfunction "PB7_43") (pintype "bidirectional"))
    )
    (net (code "11") (name "/ENC_BUTTON") (class "Default")
      (node (ref "C19") (pin "1") (pinfunction "1_1") (pintype "passive"))
      (node (ref "P3") (pin "3") (pinfunction "3_3") (pintype "passive"))
      (node (ref "R15") (pin "2") (pinfunction "2_2") (pintype "passive"))
      (node (ref "U2") (pin "12") (pinfunction "PA2_12") (pintype "bidirectional"))
    )
    (net (code "12") (name "/FAN_HEAT") (class "Default")
      (node (ref "J8") (pin "1") (pinfunction "1_1") (pintype "passive"))
      (node (ref "R23") (pin "2") (pinfunction "2_2") (pintype "passive"))
      (node (ref "U2") (pin "18") (pinfunction "PB0_18") (pintype "bidirectional"))
    )
    (net (code "13") (name "/I2C_SCL") (class "Default")
      (node (ref "P4") (pin "2") (pinfunction "2_2") (pintype "passive"))
      (node (ref "R22") (pin "1") (pinfunction "1_1") (pintype "passive"))
      (node (ref "U2") (pin "21") (pinfunction "PB10_21") (pintype "bidirectional"))
    )
    (net (code "14") (name "/I2C_SDA") (class "Default")
      (node (ref "P4") (pin "1") (pinfunction "1_1") (pintype "passive"))
      (node (ref "R21") (pin "1") (pinfunction "1_1") (pintype "passive"))
      (node (ref "U2") (pin "22") (pinfunction "PB11_22") (pintype "bidirectional"))
    )
    (net (code "15") (name "/PID_CTRL") (class "Default")
      (node (ref "J7") (pin "1") (pinfunction "1_1") (pintype "passive"))
      (node (ref "R20") (pin "2") (pinfunction "2_2") (pintype "passive"))
      (node (ref "U2") (pin "11") (pinfunction "PA1_11") (pintype "bidirectional"))
    )
    (net (code "16") (name "/RESET_PIN") (class "Default")
      (node (ref "P2") (pin "10") (pinfunction "10_10") (pintype "passive"))
      (node (ref "R4") (pin "2") (pinfunction "2_2") (pintype "passive"))
      (node (ref "SW1") (pin "2") (pinfunction "2_2") (pintype "passive"))
    )
    (net (code "17") (name "/SPI1_CS_TC1") (class "Default")
      (node (ref "R7") (pin "1") (pinfunction "1_1") (pintype "passive"))
      (node (ref "U4") (pin "6") (pinfunction "~{CS}_6") (pintype "input"))
    )
    (net (code "18") (name "/SPI1_CS_TC1_R") (class "Default")
      (node (ref "R7") (pin "2") (pinfunction "2_2") (pintype "passive"))
      (node (ref "U2") (pin "14") (pinfunction "PA4_14") (pintype "bidirectional"))
    )
    (net (code "19") (name "/SPI1_CS_TC2") (class "Default")
      (node (ref "R11") (pin "1") (pinfunction "1_1") (pintype "passive"))
      (node (ref "U5") (pin "6") (pinfunction "~{CS}_6") (pintype "input"))
    )
    (net (code "20") (name "/SPI1_CS_TC2_R") (class "Default")
      (node (ref "R11") (pin "2") (pinfunction "2_2") (pintype "passive"))
      (node (ref "U2") (pin "38") (pinfunction "PA15_38") (pintype "bidirectional"))
    )
    (net (code "21") (name "/SPI1_MISO") (class "Default")
      (node (ref "R19") (pin "2") (pinfunction "2_2") (pintype "passive"))
      (node (ref "R24") (pin "2") (pinfunction "2_2") (pintype "passive"))
      (node (ref "U2") (pin "16") (pinfunction "PA6_16") (pintype "bidirectional"))
    )
    (net (code "22") (name "/SPI1_MISO_R1") (class "Default")
      (node (ref "R24") (pin "1") (pinfunction "1_1") (pintype "passive"))
      (node (ref "U5") (pin "7") (pinfunction "SO_7") (pintype "output"))
    )
    (net (code "23") (name "/SPI1_MISO_R2") (class "Default")
      (node (ref "R19") (pin "1") (pinfunction "1_1") (pintype "passive"))
      (node (ref "U4") (pin "7") (pinfunction "SO_7") (pintype "output"))
    )
    (net (code "24") (name "/SPI1_SCK") (class "Default")
      (node (ref "R8") (pin "1") (pinfunction "1_1") (pintype "passive"))
      (node (ref "U4") (pin "5") (pinfunction "SCK_5") (pintype "input"))
      (node (ref "U5") (pin "5") (pinfunction "SCK_5") (pintype "input"))
    )
    (net (code "25") (name "/SPI1_SCK_R") (class "Default")
      (node (ref "R8") (pin "2") (pinfunction "2_2") (pintype "passive"))
      (node (ref "U2") (pin "15") (pinfunction "PA5_15") (pintype "bidirectional"))
    )
    (net (code "26") (name "/SWD_CLK") (class "Default")
      (node (ref "P2") (pin "4") (pinfunction "4_4") (pintype "passive"))
      (node (ref "R10") (pin "2") (pinfunction "2_2") (pintype "passive"))
      (node (ref "U2") (pin "37") (pinfunction "PA14_37") (pintype "bidirectional"))
    )
    (net (code "27") (name "/SWD_DIO") (class "Default")
      (node (ref "P2") (pin "2") (pinfunction "2_2") (pintype "passive"))
      (node (ref "R6") (pin "1") (pinfunction "1_1") (pintype "passive"))
      (node (ref "U2") (pin "34") (pinfunction "PA13_34") (pintype "bidirectional"))
    )
    (net (code "28") (name "/T+") (class "Default")
      (node (ref "J3") (pin "4") (pinfunction "4_4") (pintype "passive"))
      (node (ref "L1") (pin "1") (pinfunction "1_1") (pintype "passive"))
    )
    (net (code "29") (name "/T-") (class "Default")
      (node (ref "J3") (pin "3") (pinfunction "3_3") (pintype "passive"))
      (node (ref "L2") (pin "1") (pinfunction "1_1") (pintype "passive"))
    )
    (net (code "30") (name "/USB_N") (class "Default")
      (node (ref "P1") (pin "2") (pinfunction "2_2") (pintype "passive"))
      (node (ref "U2") (pin "32") (pinfunction "PA11_32") (pintype "bidirectional"))
    )
    (net (code "31") (name "/USB_P") (class "Default")
      (node (ref "P1") (pin "3") (pinfunction "3_3") (pintype "passive"))
      (node (ref "U2") (pin "33") (pinfunction "PA12_33") (pintype "bidirectional"))
    )
    (net (code "32") (name "/ZERO_DET") (class "Default")
      (node (ref "J6") (pin "1") (pinfunction "1_1") (pintype "passive"))
      (node (ref "R14") (pin "2") (pinfunction "2_2") (pintype "passive"))
      (node (ref "U2") (pin "10") (pinfunction "PA0-WKUP_10") (pintype "bidirectional"))
    )
    (net (code "33") (name "GND") (class "Default")
      (node (ref "C1") (pin "2") (pinfunction "2_2") (pintype "passive"))
      (node (ref "C10") (pin "2") (pinfunction "2_2") (pintype "passive"))
      (node (ref "C11") (pin "1") (pinfunction "C_1") (pintype "passive"))
      (node (ref "C12") (pin "2") (pinfunction "2_2") (pintype "passive"))
      (node (ref "C13") (pin "2") (pinfunction "2_2") (pintype "passive"))
      (node (ref "C14") (pin "2") (pinfunction "2_2") (pintype "passive"))
      (node (ref "C15") (pin "1") (pinfunction "1_1") (pintype "passive"))
      (node (ref "C16") (pin "1") (pinfunction "1_1") (pintype "passive"))
      (node (ref "C17") (pin "2") (pinfunction "2_2") (pintype "passive"))
      (node (ref "C18") (pin "2") (pinfunction "2_2") (pintype "passive"))
      (node (ref "C19") (pin "2") (pinfunction "2_2") (pintype "passive"))
      (node (ref "C2") (pin "2") (pinfunction "2_2") (pintype "passive"))
      (node (ref "C21") (pin "2") (pinfunction "2_2") (pintype "passive"))
      (node (ref "C23") (pin "2") (pinfunction "2_2") (pintype "passive"))
      (node (ref "C24") (pin "2") (pinfunction "2_2") (pintype "passive"))
      (node (ref "C25") (pin "2") (pinfunction "2_2") (pintype "passive"))
      (node (ref "C26") (pin "2") (pinfunction "2_2") (pintype "passive"))
      (node (ref "C27") (pin "2") (pinfunction "2_2") (pintype "passive"))
      (node (ref "C28") (pin "2") (pinfunction "2_2") (pintype "passive"))
      (node (ref "C3") (pin "2") (pinfunction "2_2") (pintype "passive"))
      (node (ref "C30") (pin "2") (pinfunction "2_2") (pintype "passive"))
      (node (ref "C31") (pin "1") (pinfunction "C_1") (pintype "passive"))
      (node (ref "C32") (pin "2") (pinfunction "2_2") (pintype "passive"))
      (node (ref "C4") (pin "2") (pinfunction "2_2") (pintype "passive"))
      (node (ref "C5") (pin "2") (pinfunction "2_2") (pintype "passive"))
      (node (ref "C6") (pin "2") (pinfunction "2_2") (pintype "passive"))
      (node (ref "C7") (pin "2") (pinfunction "2_2") (pintype "passive"))
      (node (ref "C8") (pin "2") (pinfunction "2_2") (pintype "passive"))
      (node (ref "C9") (pin "2") (pinfunction "2_2") (pintype "passive"))
      (node (ref "D1") (pin "2") (pinfunction "+_2") (pintype "passive"))
      (node (ref "D3") (pin "1") (pinfunction "C_1") (pintype "passive"))
      (node (ref "J11") (pin "2") (pinfunction "2_2") (pintype "passive"))
      (node (ref "J5") (pin "2") (pinfunction "2_2") (pintype "passive"))
      (node (ref "J9") (pin "1") (pinfunction "1_1") (pintype "passive"))
      (node (ref "P1") (pin "4") (pinfunction "4_4") (pintype "passive"))
      (node (ref "P1") (pin "5") (pinfunction "5_5") (pintype "passive"))
      (node (ref "P2") (pin "3") (pinfunction "3_3") (pintype "passive"))
      (node (ref "P2") (pin "5") (pinfunction "5_5") (pintype "passive"))
      (node (ref "P2") (pin "7") (pinfunction "7_7") (pintype "passive"))
      (node (ref "P2") (pin "9") (pinfunction "9_9") (pintype "passive"))
      (node (ref "P3") (pin "2") (pinfunction "2_2") (pintype "passive"))
      (node (ref "P4") (pin "4") (pinfunction "4_4") (pintype "passive"))
      (node (ref "Q1") (pin "2") (pinfunction "C_2") (pintype "passive"))
      (node (ref "Q3") (pin "2") (pinfunction "E_2") (pintype "passive"))
      (node (ref "R10") (pin "1") (pinfunction "1_1") (pintype "passive"))
      (node (ref "R16") (pin "2") (pinfunction "2_2") (pintype "passive"))
      (node (ref "R2") (pin "2") (pinfunction "2_2") (pintype "passive"))
      (node (ref "R26") (pin "2") (pinfunction "2_2") (pintype "passive"))
      (node (ref "R9") (pin "3") (pinfunction "TAP_3") (pintype "passive"))
      (node (ref "SW1") (pin "1") (pinfunction "1_1") (pintype "passive"))
      (node (ref "U1") (pin "1") (pinfunction "GND_1") (pintype "power_in"))
      (node (ref "U2") (pin "23") (pinfunction "VSS_1_23") (pintype "power_in"))
      (node (ref "U2") (pin "35") (pinfunction "VSS_2_35") (pintype "power_in"))
      (node (ref "U2") (pin "47") (pinfunction "VSS_3_47") (pintype "power_in"))
      (node (ref "U2") (pin "8") (pinfunction "VSSA_8") (pintype "power_in"))
      (node (ref "U4") (pin "1") (pinfunction "GND_1") (pintype "power_in"))
      (node (ref "U5") (pin "1") (pinfunction "GND_1") (pintype "power_in"))
    )
    (net (code "34") (name "Net-(C16-Pad2)") (class "Default")
      (node (ref "C16") (pin "2") (pinfunction "2_2") (pintype "passive"))
      (node (ref "R13") (pin "2") (pinfunction "2_2") (pintype "passive"))
      (node (ref "Y1") (pin "1") (pinfunction "1_1") (pintype "passive"))
    )
    (net (code "35") (name "Net-(D2-G)") (class "Default")
      (node (ref "D2") (pin "3") (pinfunction "G_3") (pintype "passive"))
      (node (ref "Q2") (pin "4") (pinfunction "1_MAIN_TERM_4") (pintype "passive"))
    )
    (net (code "36") (name "Net-(D2-MT1)") (class "Default")
      (node (ref "D2") (pin "1") (pinfunction "MT1_1") (pintype "passive"))
      (node (ref "J3") (pin "1") (pinfunction "1_1") (pintype "passive"))
    )
    (net (code "37") (name "Net-(J4-Pad1)") (class "Default")
      (node (ref "J4") (pin "1") (pinfunction "1_1") (pintype "passive"))
      (node (ref "L4") (pin "1") (pinfunction "1_1") (pintype "passive"))
    )
    (net (code "38") (name "Net-(J4-Pad2)") (class "Default")
      (node (ref "J4") (pin "2") (pinfunction "2_2") (pintype "passive"))
      (node (ref "L3") (pin "1") (pinfunction "1_1") (pintype "passive"))
    )
    (net (code "39") (name "Net-(P6-Pad1)") (class "Default")
      (node (ref "P6") (pin "1") (pinfunction "1_1") (pintype "passive"))
      (node (ref "R25") (pin "2") (pinfunction "2_2") (pintype "passive"))
      (node (ref "R26") (pin "1") (pinfunction "1_1") (pintype "passive"))
    )
    (net (code "40") (name "Net-(Q1-A)") (class "Default")
      (node (ref "Q1") (pin "1") (pinfunction "A_1") (pintype "passive"))
      (node (ref "R12") (pin "1") (pinfunction "1_1") (pintype "passive"))
    )
    (net (code "41") (name "Net-(Q1-E)") (class "Default")
      (node (ref "Q1") (pin "3") (pinfunction "E_3") (pintype "passive"))
      (node (ref "R14") (pin "1") (pinfunction "1_1") (pintype "passive"))
      (node (ref "R16") (pin "1") (pinfunction "1_1") (pintype "passive"))
    )
    (net (code "42") (name "Net-(Q2-2_MAIN_TERM)") (class "Default")
      (node (ref "Q2") (pin "6") (pinfunction "2_MAIN_TERM_6") (pintype "passive"))
      (node (ref "R18") (pin "2") (pinfunction "2_2") (pintype "passive"))
    )
    (net (code "43") (name "Net-(Q2-A)") (class "Default")
      (node (ref "Q2") (pin "1") (pinfunction "A_1") (pintype "passive"))
      (node (ref "R17") (pin "1") (pinfunction "1_1") (pintype "passive"))
    )
    (net (code "44") (name "Net-(Q2-C)") (class "Default")
      (node (ref "Q2") (pin "2") (pinfunction "C_2") (pintype "passive"))
      (node (ref "Q3") (pin "3") (pinfunction "C_3") (pintype "passive"))
    )
    (net (code "45") (name "Net-(Q3-B)") (class "Default")
      (node (ref "Q3") (pin "1") (pinfunction "B_1") (pintype "passive"))
      (node (ref "R20") (pin "1") (pinfunction "1_1") (pintype "passive"))
    )
    (net (code "46") (name "Net-(Q4-B)") (class "Default")
      (node (ref "C28") (pin "1") (pinfunction "1_1") (pintype "passive"))
      (node (ref "Q4") (pin "1") (pinfunction "B_1") (pintype "passive"))
      (node (ref "R23") (pin "1") (pinfunction "1_1") (pintype "passive"))
    )
    (net (code "47") (name "Net-(Q4-E)") (class "Default")
      (node (ref "Q4") (pin "2") (pinfunction "E_2") (pintype "passive"))
      (node (ref "Q5") (pin "1") (pinfunction "B_1") (pintype "passive"))
    )
    (net (code "48") (name "Net-(Q5-E)") (class "Default")
      (node (ref "J5") (pin "1") (pinfunction "1_1") (pintype "passive"))
      (node (ref "Q5") (pin "3") (pinfunction "E_3") (pintype "passive"))
    )
    (net (code "49") (name "Net-(Q6-B)") (class "Default")
      (node (ref "Q6") (pin "1") (pinfunction "B_1") (pintype "passive"))
      (node (ref "R25") (pin "1") (pinfunction "1_1") (pintype "passive"))
    )
    (net (code "50") (name "Net-(Q6-E)") (class "Default")
      (node (ref "C32") (pin "1") (pinfunction "1_1") (pintype "passive"))
      (node (ref "J11") (pin "1") (pinfunction "1_1") (pintype "passive"))
      (node (ref "Q6") (pin "3") (pinfunction "E_3") (pintype "passive"))
    )
    (net (code "51") (name "Net-(R9-B)") (class "Default")
      (node (ref "R5") (pin "2") (pinfunction "2_2") (pintype "passive"))
      (node (ref "R9") (pin "2") (pinfunction "B_2") (pintype "passive"))
      (node (ref "U3") (pin "1") (pinfunction "ADJ_1") (pintype "input"))
    )
    (net (code "52") (name "Net-(U2-BOOT0)") (class "Default")
      (node (ref "R2") (pin "1") (pinfunction "1_1") (pintype "passive"))
      (node (ref "U2") (pin "44") (pinfunction "BOOT0_44") (pintype "input"))
    )
    (net (code "53") (name "Net-(U2-PD0-OSC_IN)") (class "Default")
      (node (ref "C15") (pin "2") (pinfunction "2_2") (pintype "passive"))
      (node (ref "U2") (pin "5") (pinfunction "PD0-OSC_IN_5") (pintype "bidirectional"))
      (node (ref "Y1") (pin "2") (pinfunction "2_2") (pintype "passive"))
    )
    (net (code "54") (name "Net-(U2-PD1-OSC_OUT)") (class "Default")
      (node (ref "R13") (pin "1") (pinfunction "1_1") (pintype "passive"))
      (node (ref "U2") (pin "6") (pinfunction "PD1-OSC_OUT_6") (pintype "bidirectional"))
    )
    (net (code "55") (name "Net-(U2-~{RST})") (class "Default")
      (node (ref "C9") (pin "1") (pinfunction "1_1") (pintype "passive"))
      (node (ref "R3") (pin "1") (pinfunction "1_1") (pintype "passive"))
      (node (ref "R4") (pin "1") (pinfunction "1_1") (pintype "passive"))
      (node (ref "U2") (pin "7") (pinfunction "~{RST}_7") (pintype "input"))
    )
    (net (code "56") (name "Net-(U4-T+)") (class "Default")
      (node (ref "C20") (pin "1") (pinfunction "1_1") (pintype "passive"))
      (node (ref "C25") (pin "1") (pinfunction "1_1") (pintype "passive"))
      (node (ref "L1") (pin "2") (pinfunction "2_2") (pintype "passive"))
      (node (ref "U4") (pin "3") (pinfunction "T+_3") (pintype "input"))
    )
    (net (code "57") (name "Net-(U4-T-)") (class "Default")
      (node (ref "C20") (pin "2") (pinfunction "2_2") (pintype "passive"))
      (node (ref "C24") (pin "1") (pinfunction "1_1") (pintype "passive"))
      (node (ref "L2") (pin "2") (pinfunction "2_2") (pintype "passive"))
      (node (ref "U4") (pin "2") (pinfunction "T-_2") (pintype "input"))
    )
    (net (code "58") (name "Net-(U5-T+)") (class "Default")
      (node (ref "C22") (pin "1") (pinfunction "1_1") (pintype "passive"))
      (node (ref "C27") (pin "1") (pinfunction "1_1") (pintype "passive"))
      (node (ref "L3") (pin "2") (pinfunction "2_2") (pintype "passive"))
      (node (ref "U5") (pin "3") (pinfunction "T+_3") (pintype "input"))
    )
    (net (code "59") (name "Net-(U5-T-)") (class "Default")
      (node (ref "C22") (pin "2") (pinfunction "2_2") (pintype "passive"))
      (node (ref "C26") (pin "1") (pinfunction "1_1") (pintype "passive"))
      (node (ref "L4") (pin "2") (pinfunction "2_2") (pintype "passive"))
      (node (ref "U5") (pin "2") (pinfunction "T-_2") (pintype "input"))
    )
    (net (code "60") (name "unconnected-(J2-Pad5)") (class "Default")
      (node (ref "J2") (pin "5") (pinfunction "5_5") (pintype "passive"))
    )
    (net (code "61") (name "unconnected-(P1-Pad1)") (class "Default")
      (node (ref "P1") (pin "1") (pinfunction "1_1") (pintype "passive+no_connect"))
    )
    (net (code "62") (name "unconnected-(P2-Pad6)") (class "Default")
      (node (ref "P2") (pin "6") (pinfunction "6_6") (pintype "passive"))
    )
    (net (code "63") (name "unconnected-(P2-Pad8)") (class "Default")
      (node (ref "P2") (pin "8") (pinfunction "8_8") (pintype "passive"))
    )
    (net (code "64") (name "unconnected-(Q2-NC-Pad3)") (class "Default")
      (node (ref "Q2") (pin "3") (pinfunction "NC_3") (pintype "passive+no_connect"))
    )
    (net (code "65") (name "unconnected-(Q2-NC-Pad5)") (class "Default")
      (node (ref "Q2") (pin "5") (pinfunction "NC_5") (pintype "passive+no_connect"))
    )
    (net (code "66") (name "unconnected-(R9-A-Pad1)") (class "Default")
      (node (ref "R9") (pin "1") (pinfunction "A_1") (pintype "passive+no_connect"))
    )
    (net (code "67") (name "unconnected-(U2-PA3-Pad13)") (class "Default")
      (node (ref "U2") (pin "13") (pinfunction "PA3_13") (pintype "bidirectional"))
    )
    (net (code "68") (name "unconnected-(U2-PA7-Pad17)") (class "Default")
      (node (ref "U2") (pin "17") (pinfunction "PA7_17") (pintype "bidirectional"))
    )
    (net (code "69") (name "unconnected-(U2-PA8-Pad29)") (class "Default")
      (node (ref "U2") (pin "29") (pinfunction "PA8_29") (pintype "bidirectional"))
    )
    (net (code "70") (name "unconnected-(U2-PA9-Pad30)") (class "Default")
      (node (ref "U2") (pin "30") (pinfunction "PA9_30") (pintype "bidirectional"))
    )
    (net (code "71") (name "unconnected-(U2-PA10-Pad31)") (class "Default")
      (node (ref "U2") (pin "31") (pinfunction "PA10_31") (pintype "bidirectional"))
    )
    (net (code "72") (name "unconnected-(U2-PB1-Pad19)") (class "Default")
      (node (ref "U2") (pin "19") (pinfunction "PB1_19") (pintype "bidirectional"))
    )
    (net (code "73") (name "unconnected-(U2-PB2-Pad20)") (class "Default")
      (node (ref "U2") (pin "20") (pinfunction "PB2_20") (pintype "bidirectional"))
    )
    (net (code "74") (name "unconnected-(U2-PB3-Pad39)") (class "Default")
      (node (ref "U2") (pin "39") (pinfunction "PB3_39") (pintype "bidirectional"))
    )
    (net (code "75") (name "unconnected-(U2-PB4-Pad40)") (class "Default")
      (node (ref "U2") (pin "40") (pinfunction "PB4_40") (pintype "bidirectional"))
    )
    (net (code "76") (name "unconnected-(U2-PB5-Pad41)") (class "Default")
      (node (ref "U2") (pin "41") (pinfunction "PB5_41") (pintype "bidirectional"))
    )
    (net (code "77") (name "unconnected-(U2-PB8-Pad45)") (class "Default")
      (node (ref "U2") (pin "45") (pinfunction "PB8_45") (pintype "bidirectional"))
    )
    (net (code "78") (name "unconnected-(U2-PB9-Pad46)") (class "Default")
      (node (ref "U2") (pin "46") (pinfunction "PB9_46") (pintype "bidirectional"))
    )
    (net (code "79") (name "unconnected-(U2-PB12-Pad25)") (class "Default")
      (node (ref "U2") (pin "25") (pinfunction "PB12_25") (pintype "bidirectional"))
    )
    (net (code "80") (name "unconnected-(U2-PB13-Pad26)") (class "Default")
      (node (ref "U2") (pin "26") (pinfunction "PB13_26") (pintype "bidirectional"))
    )
    (net (code "81") (name "unconnected-(U2-PB14-Pad27)") (class "Default")
      (node (ref "U2") (pin "27") (pinfunction "PB14_27") (pintype "bidirectional"))
    )
    (net (code "82") (name "unconnected-(U2-PB15-Pad28)") (class "Default")
      (node (ref "U2") (pin "28") (pinfunction "PB15_28") (pintype "bidirectional"))
    )
    (net (code "83") (name "unconnected-(U2-PC13-TAMPER-RTC-Pad2)") (class "Default")
      (node (ref "U2") (pin "2") (pinfunction "PC13-TAMPER-RTC_2") (pintype "bidirectional"))
    )
    (net (code "84") (name "unconnected-(U2-PC14-OSC32_IN-Pad3)") (class "Default")
      (node (ref "U2") (pin "3") (pinfunction "PC14-OSC32_IN_3") (pintype "bidirectional"))
    )
    (net (code "85") (name "unconnected-(U2-PC15-OSC32_OUT-Pad4)") (class "Default")
      (node (ref "U2") (pin "4") (pinfunction "PC15-OSC32_OUT_4") (pintype "bidirectional"))
    )
    (net (code "86") (name "unconnected-(U2-VBAT-Pad1)") (class "Default")
      (node (ref "U2") (pin "1") (pinfunction "VBAT_1") (pintype "power_in"))
    )
    (net (code "87") (name "unconnected-(U4-DNC-Pad8)") (class "Default")
      (node (ref "U4") (pin "8") (pinfunction "DNC_8") (pintype "passive"))
    )
    (net (code "88") (name "unconnected-(U5-DNC-Pad8)") (class "Default")
      (node (ref "U5") (pin "8") (pinfunction "DNC_8") (pintype "passive"))
    )
    (net (code "89") (name "~230") (class "Default")
      (node (ref "C29") (pin "2") (pinfunction "2_2") (pintype "passive"))
      (node (ref "D2") (pin "2") (pinfunction "MT2_2") (pintype "passive"))
      (node (ref "J1") (pin "1") (pinfunction "1_1") (pintype "passive"))
      (node (ref "J1") (pin "2") (pinfunction "2_2") (pintype "passive"))
      (node (ref "R1") (pin "2") (pinfunction "2_2") (pintype "passive"))
      (node (ref "R18") (pin "1") (pinfunction "1_1") (pintype "passive"))
    )
    (net (code "90") (name "~N") (class "Default")
      (node (ref "C29") (pin "1") (pinfunction "1_1") (pintype "passive"))
      (node (ref "J1") (pin "3") (pinfunction "3_3") (pintype "passive"))
      (node (ref "J1") (pin "4") (pinfunction "4_4") (pintype "passive"))
      (node (ref "J3") (pin "2") (pinfunction "2_2") (pintype "passive"))
      (node (ref "R1") (pin "1") (pinfunction "1_1") (pintype "passive"))
    )
  )
)
